# SCH_New_Hacker_Card_2024-08-23.net
KiCad netlist of a schematic drawn in EasyEDA
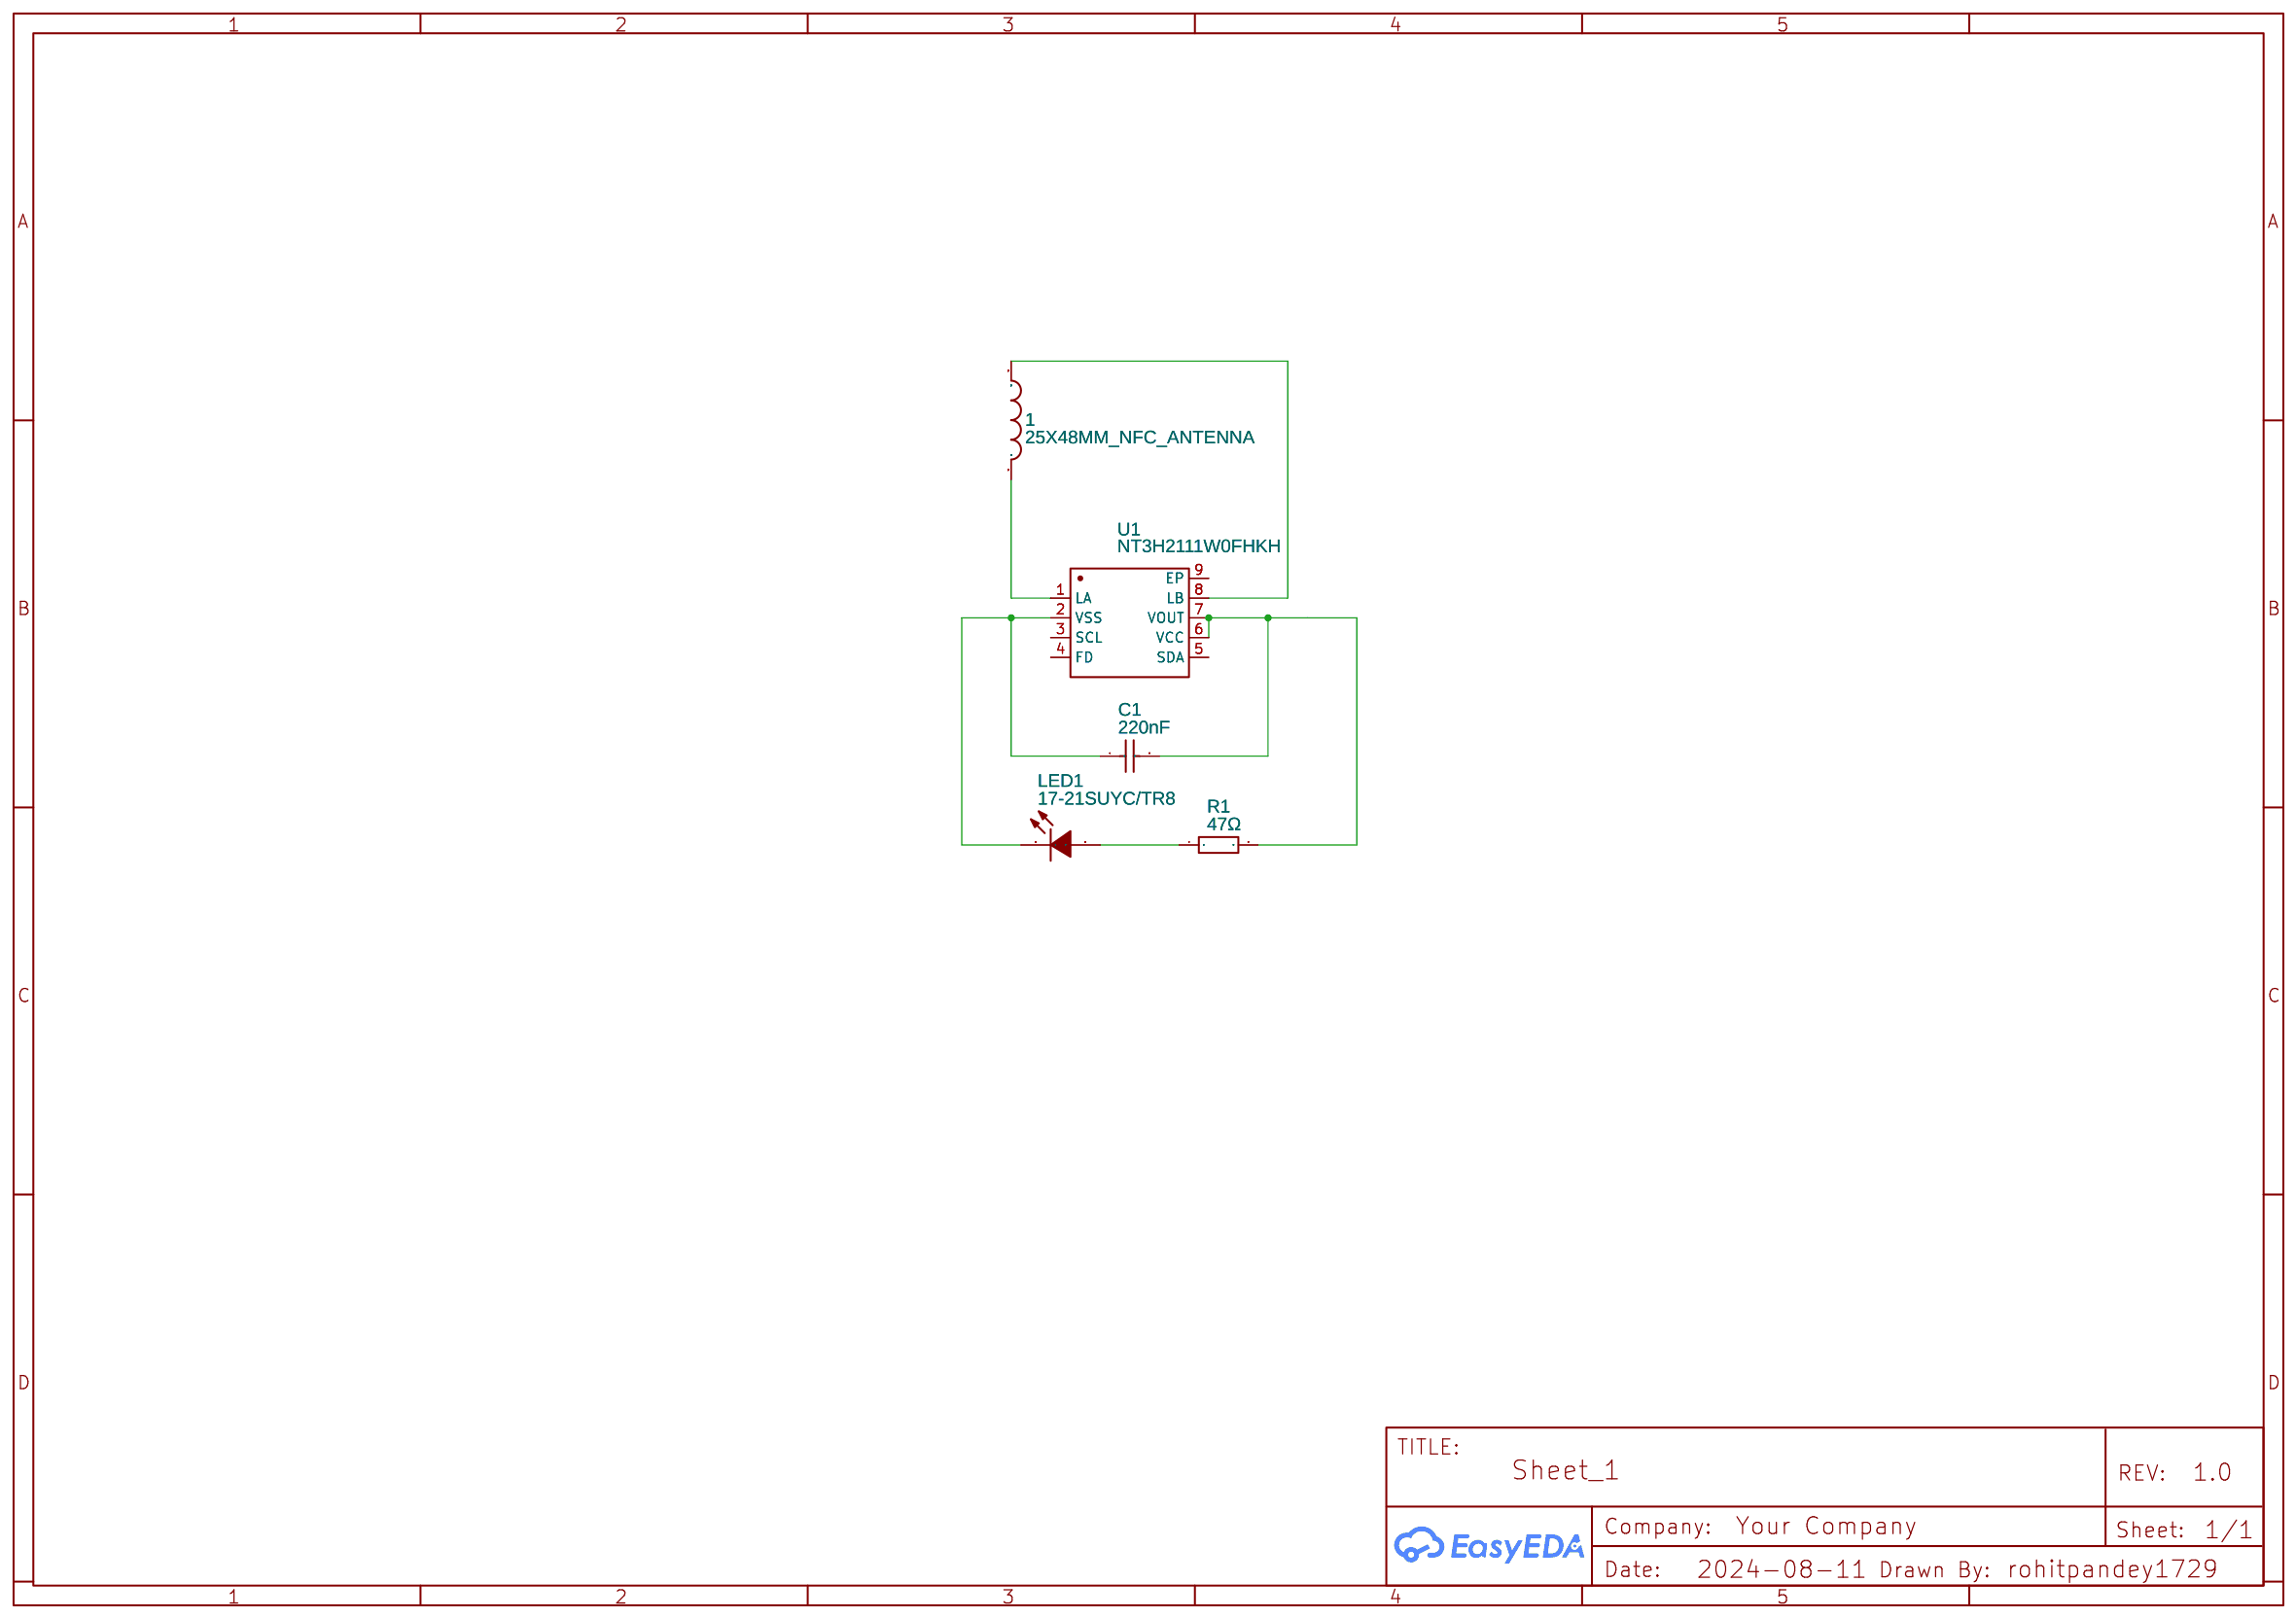
[diagram p0: schematic sheet]

(export (version "E")
  (design (tool "Eeschema 10.0.6"))
  (components
    (comp (ref "1") (value "25X48MM_NFC_ANTENNA") (libsource (lib "") (part "25X48MM_NFC_ANTENNA")))
    (comp (ref "C1")
      (value "220nF")
      (fields
        (field (name "Manufacturer Part") "CL10B224KA8NNNC")
        (field (name "Manufacturer") "SAMSUNG(三星)")
      )
      (libsource (lib "") (part "CL10B224KA8NNNC"))
    )
    (comp (ref "LED1")
      (value "17-21SUYC/TR8")
      (fields (field (name "Manufacturer Part") "KT-0805黄灯") (field (name "Manufacturer") "KENTO"))
      (libsource (lib "") (part "17-21SUYC/TR8"))
    )
    (comp (ref "R1")
      (value "47Ω")
      (fields
        (field (name "Manufacturer Part") "0603WAF470JT5E")
        (field (name "Manufacturer") "UNI-ROYAL(厚声)")
      )
      (libsource (lib "") (part "0603WAF470JT5E"))
    )
    (comp (ref "U1")
      (value "NT3H2111W0FHKH")
      (fields (field (name "Manufacturer") "NXP(恩智浦)"))
      (libsource (lib "") (part "NT3H2111W0FHKH"))
    )
  )
  (nets
    (net (code "1") (name "Net-(LED1-+)") (class "Default")
      (node (ref "LED1") (pin "1") (pinfunction "+_1") (pintype "unspecified"))
      (node (ref "R1") (pin "1") (pinfunction "1_1") (pintype "input"))
    )
    (net (code "2") (name "Net-(LED1--)") (class "Default")
      (node (ref "C1") (pin "1") (pinfunction "1_1") (pintype "input"))
      (node (ref "LED1") (pin "2") (pinfunction "-_2") (pintype "unspecified"))
      (node (ref "U1") (pin "2") (pinfunction "VSS_2") (pintype "unspecified"))
    )
    (net (code "3") (name "Net-(U1-LA)") (class "Default")
      (node (ref "1") (pin "P$2") (pinfunction "P$2_P$2") (pintype "bidirectional"))
      (node (ref "U1") (pin "1") (pinfunction "LA_1") (pintype "unspecified"))
    )
    (net (code "4") (name "Net-(U1-LB)") (class "Default")
      (node (ref "1") (pin "P$1") (pinfunction "P$1_P$1") (pintype "bidirectional"))
      (node (ref "U1") (pin "8") (pinfunction "LB_8") (pintype "unspecified"))
    )
    (net (code "5") (name "Net-(U1-VCC)") (class "Default")
      (node (ref "C1") (pin "2") (pinfunction "2_2") (pintype "input"))
      (node (ref "R1") (pin "2") (pinfunction "2_2") (pintype "input"))
      (node (ref "U1") (pin "6") (pinfunction "VCC_6") (pintype "unspecified"))
      (node (ref "U1") (pin "7") (pinfunction "VOUT_7") (pintype "unspecified"))
    )
    (net (code "6") (name "unconnected-(U1-EP-Pad9)") (class "Default")
      (node (ref "U1") (pin "9") (pinfunction "EP_9") (pintype "unspecified"))
    )
    (net (code "7") (name "unconnected-(U1-FD-Pad4)") (class "Default")
      (node (ref "U1") (pin "4") (pinfunction "FD_4") (pintype "unspecified"))
    )
    (net (code "8") (name "unconnected-(U1-SCL-Pad3)") (class "Default")
      (node (ref "U1") (pin "3") (pinfunction "SCL_3") (pintype "unspecified"))
    )
    (net (code "9") (name "unconnected-(U1-SDA-Pad5)") (class "Default")
      (node (ref "U1") (pin "5") (pinfunction "SDA_5") (pintype "unspecified"))
    )
  )
)
